# pixel-mk-1_0.net
KiCad netlist of a schematic drawn in EAGLE
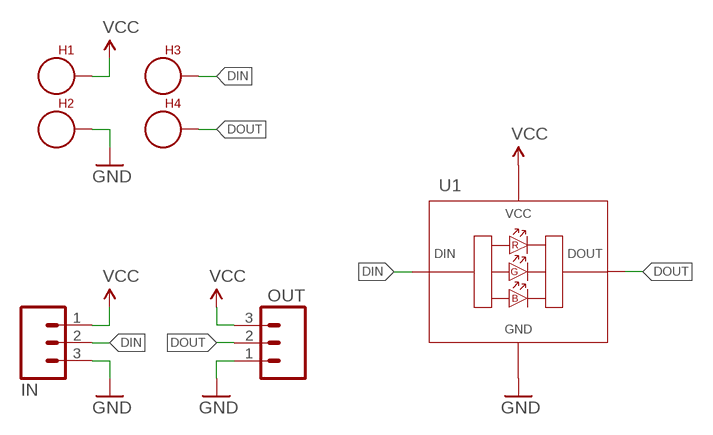
[diagram p0: schematic, sheet 1]

(export (version "E")
  (design (tool "Eeschema 10.0.6"))
  (components
    (comp (ref "H1")
      (value "SEW_HOLE")
      (footprint "eagle-import:SIMPLE_HOLE")
      (libsource (lib "eagle-import") (part "SEW_HOLE"))
    )
    (comp (ref "H2")
      (value "SEW_HOLE")
      (footprint "eagle-import:SIMPLE_HOLE")
      (libsource (lib "eagle-import") (part "SEW_HOLE"))
    )
    (comp (ref "H3")
      (value "SEW_HOLE")
      (footprint "eagle-import:SIMPLE_HOLE")
      (libsource (lib "eagle-import") (part "SEW_HOLE"))
    )
    (comp (ref "H4")
      (value "SEW_HOLE")
      (footprint "eagle-import:SIMPLE_HOLE")
      (libsource (lib "eagle-import") (part "SEW_HOLE"))
    )
    (comp (ref "IN")
      (value "M03JST-PTH")
      (footprint "eagle-import:JST-3-PH-RA-PTH")
      (libsource (lib "eagle-import") (part "M03JST-PTH"))
    )
    (comp (ref "OUT")
      (value "M03JST-PTH")
      (footprint "eagle-import:JST-3-PH-RA-PTH")
      (libsource (lib "eagle-import") (part "M03JST-PTH"))
    )
    (comp (ref "U1")
      (value "NEOPIXEL5MM-PTH-RA-NS")
      (footprint "eagle-import:LED-5MM-PTH-FUCK-RA-NS")
      (libsource (lib "eagle-import") (part "NEOPIXEL5MM-PTH-RA-NS"))
    )
  )
  (nets
    (net (code "1") (name "DIN") (class "Default")
      (node (ref "H3") (pin "P$1") (pinfunction "P$1_P$1") (pintype "bidirectional"))
      (node (ref "IN") (pin "2") (pinfunction "2_2") (pintype "passive"))
      (node (ref "U1") (pin "1") (pinfunction "DIN_1") (pintype "bidirectional"))
    )
    (net (code "2") (name "DOUT") (class "Default")
      (node (ref "H4") (pin "P$1") (pinfunction "P$1_P$1") (pintype "bidirectional"))
      (node (ref "OUT") (pin "2") (pinfunction "2_2") (pintype "passive"))
      (node (ref "U1") (pin "4") (pinfunction "DOUT_4") (pintype "bidirectional"))
    )
    (net (code "3") (name "GND") (class "Default")
      (node (ref "H2") (pin "P$1") (pinfunction "P$1_P$1") (pintype "bidirectional"))
      (node (ref "IN") (pin "3") (pinfunction "3_3") (pintype "passive"))
      (node (ref "OUT") (pin "1") (pinfunction "1_1") (pintype "passive"))
      (node (ref "U1") (pin "3") (pinfunction "GND_3") (pintype "bidirectional"))
    )
    (net (code "4") (name "VCC") (class "Default")
      (node (ref "H1") (pin "P$1") (pinfunction "P$1_P$1") (pintype "bidirectional"))
      (node (ref "IN") (pin "1") (pinfunction "1_1") (pintype "passive"))
      (node (ref "OUT") (pin "3") (pinfunction "3_3") (pintype "passive"))
      (node (ref "U1") (pin "2") (pinfunction "VCC_2") (pintype "bidirectional"))
    )
  )
)
